# kbd.net
KiCad netlist of a schematic drawn in Altium Designer
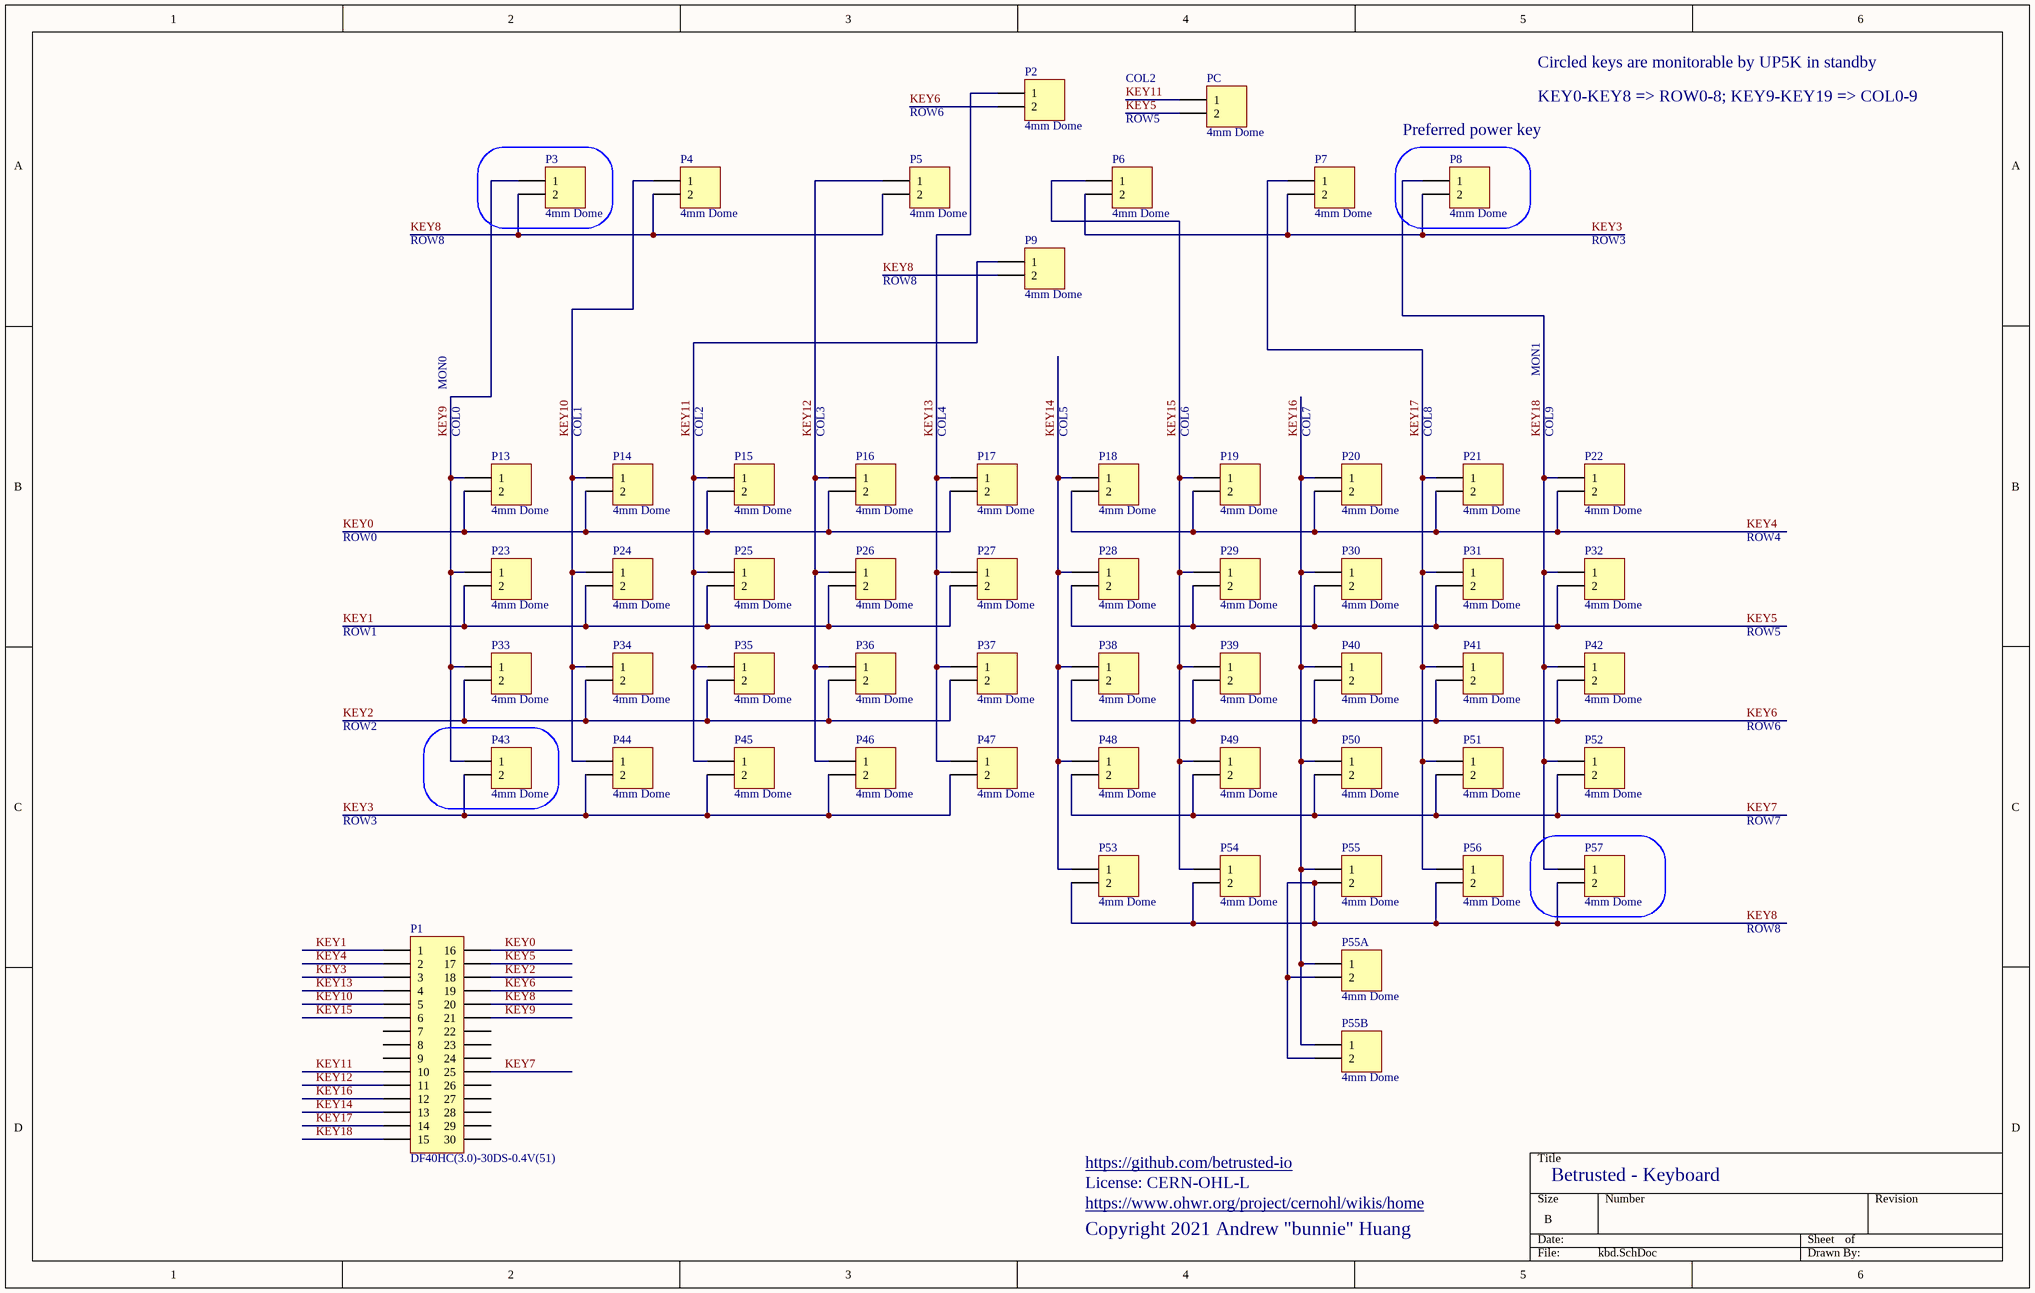
[diagram p0: kbd.SchDoc]

(export (version "E")
  (design (tool "Eeschema 10.0.6"))
  (components
    (comp (ref "P1")
      (value "DF40HC(3.0)-30DS-0.4V(51)")
      (footprint "HRS_DF40HC(3.0)-30DS-0.4V(51)")
      (description "Header, 15-Pin, Dual row")
      (fields (field (name "PUBLISHER") "Altium Limited"))
      (libsource (lib "Miscellaneous Connectors") (part "Header 15X2A"))
    )
    (comp (ref "P2")
      (value "4mm Dome")
      (footprint "4MM_DOME_SW")
      (description "Header, 2-Pin")
      (fields (field (name "PUBLISHER") "Altium Limited"))
      (libsource (lib "Miscellaneous Connectors") (part "Header 2"))
    )
    (comp (ref "P3")
      (value "4mm Dome")
      (footprint "4MM_DOME_SW")
      (description "Header, 2-Pin")
      (fields (field (name "PUBLISHER") "Altium Limited"))
      (libsource (lib "Miscellaneous Connectors") (part "Header 2"))
    )
    (comp (ref "P4")
      (value "4mm Dome")
      (footprint "4MM_DOME_SW")
      (description "Header, 2-Pin")
      (fields (field (name "PUBLISHER") "Altium Limited"))
      (libsource (lib "Miscellaneous Connectors") (part "Header 2"))
    )
    (comp (ref "P5")
      (value "4mm Dome")
      (footprint "4MM_DOME_SW")
      (description "Header, 2-Pin")
      (fields (field (name "PUBLISHER") "Altium Limited"))
      (libsource (lib "Miscellaneous Connectors") (part "Header 2"))
    )
    (comp (ref "P6")
      (value "4mm Dome")
      (footprint "4MM_DOME_SW")
      (description "Header, 2-Pin")
      (fields (field (name "PUBLISHER") "Altium Limited"))
      (libsource (lib "Miscellaneous Connectors") (part "Header 2"))
    )
    (comp (ref "P7")
      (value "4mm Dome")
      (footprint "4MM_DOME_SW")
      (description "Header, 2-Pin")
      (fields (field (name "PUBLISHER") "Altium Limited"))
      (libsource (lib "Miscellaneous Connectors") (part "Header 2"))
    )
    (comp (ref "P8")
      (value "4mm Dome")
      (footprint "4MM_DOME_SW")
      (description "Header, 2-Pin")
      (fields (field (name "PUBLISHER") "Altium Limited"))
      (libsource (lib "Miscellaneous Connectors") (part "Header 2"))
    )
    (comp (ref "P9")
      (value "4mm Dome")
      (footprint "4MM_DOME_SW")
      (description "Header, 2-Pin")
      (fields (field (name "PUBLISHER") "Altium Limited"))
      (libsource (lib "Miscellaneous Connectors") (part "Header 2"))
    )
    (comp (ref "P13")
      (value "4mm Dome")
      (footprint "4MM_DOME_SW")
      (description "Header, 2-Pin")
      (fields (field (name "PUBLISHER") "Altium Limited"))
      (libsource (lib "Miscellaneous Connectors") (part "Header 2"))
    )
    (comp (ref "P14")
      (value "4mm Dome")
      (footprint "4MM_DOME_SW")
      (description "Header, 2-Pin")
      (fields (field (name "PUBLISHER") "Altium Limited"))
      (libsource (lib "Miscellaneous Connectors") (part "Header 2"))
    )
    (comp (ref "P15")
      (value "4mm Dome")
      (footprint "4MM_DOME_SW")
      (description "Header, 2-Pin")
      (fields (field (name "PUBLISHER") "Altium Limited"))
      (libsource (lib "Miscellaneous Connectors") (part "Header 2"))
    )
    (comp (ref "P16")
      (value "4mm Dome")
      (footprint "4MM_DOME_SW")
      (description "Header, 2-Pin")
      (fields (field (name "PUBLISHER") "Altium Limited"))
      (libsource (lib "Miscellaneous Connectors") (part "Header 2"))
    )
    (comp (ref "P17")
      (value "4mm Dome")
      (footprint "4MM_DOME_SW")
      (description "Header, 2-Pin")
      (fields (field (name "PUBLISHER") "Altium Limited"))
      (libsource (lib "Miscellaneous Connectors") (part "Header 2"))
    )
    (comp (ref "P18")
      (value "4mm Dome")
      (footprint "4MM_DOME_SW")
      (description "Header, 2-Pin")
      (fields (field (name "PUBLISHER") "Altium Limited"))
      (libsource (lib "Miscellaneous Connectors") (part "Header 2"))
    )
    (comp (ref "P19")
      (value "4mm Dome")
      (footprint "4MM_DOME_SW")
      (description "Header, 2-Pin")
      (fields (field (name "PUBLISHER") "Altium Limited"))
      (libsource (lib "Miscellaneous Connectors") (part "Header 2"))
    )
    (comp (ref "P20")
      (value "4mm Dome")
      (footprint "4MM_DOME_SW")
      (description "Header, 2-Pin")
      (fields (field (name "PUBLISHER") "Altium Limited"))
      (libsource (lib "Miscellaneous Connectors") (part "Header 2"))
    )
    (comp (ref "P21")
      (value "4mm Dome")
      (footprint "4MM_DOME_SW")
      (description "Header, 2-Pin")
      (fields (field (name "PUBLISHER") "Altium Limited"))
      (libsource (lib "Miscellaneous Connectors") (part "Header 2"))
    )
    (comp (ref "P22")
      (value "4mm Dome")
      (footprint "4MM_DOME_SW")
      (description "Header, 2-Pin")
      (fields (field (name "PUBLISHER") "Altium Limited"))
      (libsource (lib "Miscellaneous Connectors") (part "Header 2"))
    )
    (comp (ref "P23")
      (value "4mm Dome")
      (footprint "4MM_DOME_SW")
      (description "Header, 2-Pin")
      (fields (field (name "PUBLISHER") "Altium Limited"))
      (libsource (lib "Miscellaneous Connectors") (part "Header 2"))
    )
    (comp (ref "P24")
      (value "4mm Dome")
      (footprint "4MM_DOME_SW")
      (description "Header, 2-Pin")
      (fields (field (name "PUBLISHER") "Altium Limited"))
      (libsource (lib "Miscellaneous Connectors") (part "Header 2"))
    )
    (comp (ref "P25")
      (value "4mm Dome")
      (footprint "4MM_DOME_SW")
      (description "Header, 2-Pin")
      (fields (field (name "PUBLISHER") "Altium Limited"))
      (libsource (lib "Miscellaneous Connectors") (part "Header 2"))
    )
    (comp (ref "P26")
      (value "4mm Dome")
      (footprint "4MM_DOME_SW")
      (description "Header, 2-Pin")
      (fields (field (name "PUBLISHER") "Altium Limited"))
      (libsource (lib "Miscellaneous Connectors") (part "Header 2"))
    )
    (comp (ref "P27")
      (value "4mm Dome")
      (footprint "4MM_DOME_SW")
      (description "Header, 2-Pin")
      (fields (field (name "PUBLISHER") "Altium Limited"))
      (libsource (lib "Miscellaneous Connectors") (part "Header 2"))
    )
    (comp (ref "P28")
      (value "4mm Dome")
      (footprint "4MM_DOME_SW")
      (description "Header, 2-Pin")
      (fields (field (name "PUBLISHER") "Altium Limited"))
      (libsource (lib "Miscellaneous Connectors") (part "Header 2"))
    )
    (comp (ref "P29")
      (value "4mm Dome")
      (footprint "4MM_DOME_SW")
      (description "Header, 2-Pin")
      (fields (field (name "PUBLISHER") "Altium Limited"))
      (libsource (lib "Miscellaneous Connectors") (part "Header 2"))
    )
    (comp (ref "P30")
      (value "4mm Dome")
      (footprint "4MM_DOME_SW")
      (description "Header, 2-Pin")
      (fields (field (name "PUBLISHER") "Altium Limited"))
      (libsource (lib "Miscellaneous Connectors") (part "Header 2"))
    )
    (comp (ref "P31")
      (value "4mm Dome")
      (footprint "4MM_DOME_SW")
      (description "Header, 2-Pin")
      (fields (field (name "PUBLISHER") "Altium Limited"))
      (libsource (lib "Miscellaneous Connectors") (part "Header 2"))
    )
    (comp (ref "P32")
      (value "4mm Dome")
      (footprint "4MM_DOME_SW")
      (description "Header, 2-Pin")
      (fields (field (name "PUBLISHER") "Altium Limited"))
      (libsource (lib "Miscellaneous Connectors") (part "Header 2"))
    )
    (comp (ref "P33")
      (value "4mm Dome")
      (footprint "4MM_DOME_SW")
      (description "Header, 2-Pin")
      (fields (field (name "PUBLISHER") "Altium Limited"))
      (libsource (lib "Miscellaneous Connectors") (part "Header 2"))
    )
    (comp (ref "P34")
      (value "4mm Dome")
      (footprint "4MM_DOME_SW")
      (description "Header, 2-Pin")
      (fields (field (name "PUBLISHER") "Altium Limited"))
      (libsource (lib "Miscellaneous Connectors") (part "Header 2"))
    )
    (comp (ref "P35")
      (value "4mm Dome")
      (footprint "4MM_DOME_SW")
      (description "Header, 2-Pin")
      (fields (field (name "PUBLISHER") "Altium Limited"))
      (libsource (lib "Miscellaneous Connectors") (part "Header 2"))
    )
    (comp (ref "P36")
      (value "4mm Dome")
      (footprint "4MM_DOME_SW")
      (description "Header, 2-Pin")
      (fields (field (name "PUBLISHER") "Altium Limited"))
      (libsource (lib "Miscellaneous Connectors") (part "Header 2"))
    )
    (comp (ref "P37")
      (value "4mm Dome")
      (footprint "4MM_DOME_SW")
      (description "Header, 2-Pin")
      (fields (field (name "PUBLISHER") "Altium Limited"))
      (libsource (lib "Miscellaneous Connectors") (part "Header 2"))
    )
    (comp (ref "P38")
      (value "4mm Dome")
      (footprint "4MM_DOME_SW")
      (description "Header, 2-Pin")
      (fields (field (name "PUBLISHER") "Altium Limited"))
      (libsource (lib "Miscellaneous Connectors") (part "Header 2"))
    )
    (comp (ref "P39")
      (value "4mm Dome")
      (footprint "4MM_DOME_SW")
      (description "Header, 2-Pin")
      (fields (field (name "PUBLISHER") "Altium Limited"))
      (libsource (lib "Miscellaneous Connectors") (part "Header 2"))
    )
    (comp (ref "P40")
      (value "4mm Dome")
      (footprint "4MM_DOME_SW")
      (description "Header, 2-Pin")
      (fields (field (name "PUBLISHER") "Altium Limited"))
      (libsource (lib "Miscellaneous Connectors") (part "Header 2"))
    )
    (comp (ref "P41")
      (value "4mm Dome")
      (footprint "4MM_DOME_SW")
      (description "Header, 2-Pin")
      (fields (field (name "PUBLISHER") "Altium Limited"))
      (libsource (lib "Miscellaneous Connectors") (part "Header 2"))
    )
    (comp (ref "P42")
      (value "4mm Dome")
      (footprint "4MM_DOME_SW")
      (description "Header, 2-Pin")
      (fields (field (name "PUBLISHER") "Altium Limited"))
      (libsource (lib "Miscellaneous Connectors") (part "Header 2"))
    )
    (comp (ref "P43")
      (value "4mm Dome")
      (footprint "4MM_DOME_SW")
      (description "Header, 2-Pin")
      (fields (field (name "PUBLISHER") "Altium Limited"))
      (libsource (lib "Miscellaneous Connectors") (part "Header 2"))
    )
    (comp (ref "P44")
      (value "4mm Dome")
      (footprint "4MM_DOME_SW")
      (description "Header, 2-Pin")
      (fields (field (name "PUBLISHER") "Altium Limited"))
      (libsource (lib "Miscellaneous Connectors") (part "Header 2"))
    )
    (comp (ref "P45")
      (value "4mm Dome")
      (footprint "4MM_DOME_SW")
      (description "Header, 2-Pin")
      (fields (field (name "PUBLISHER") "Altium Limited"))
      (libsource (lib "Miscellaneous Connectors") (part "Header 2"))
    )
    (comp (ref "P46")
      (value "4mm Dome")
      (footprint "4MM_DOME_SW")
      (description "Header, 2-Pin")
      (fields (field (name "PUBLISHER") "Altium Limited"))
      (libsource (lib "Miscellaneous Connectors") (part "Header 2"))
    )
    (comp (ref "P47")
      (value "4mm Dome")
      (footprint "4MM_DOME_SW")
      (description "Header, 2-Pin")
      (fields (field (name "PUBLISHER") "Altium Limited"))
      (libsource (lib "Miscellaneous Connectors") (part "Header 2"))
    )
    (comp (ref "P48")
      (value "4mm Dome")
      (footprint "4MM_DOME_SW")
      (description "Header, 2-Pin")
      (fields (field (name "PUBLISHER") "Altium Limited"))
      (libsource (lib "Miscellaneous Connectors") (part "Header 2"))
    )
    (comp (ref "P49")
      (value "4mm Dome")
      (footprint "4MM_DOME_SW")
      (description "Header, 2-Pin")
      (fields (field (name "PUBLISHER") "Altium Limited"))
      (libsource (lib "Miscellaneous Connectors") (part "Header 2"))
    )
    (comp (ref "P50")
      (value "4mm Dome")
      (footprint "4MM_DOME_SW")
      (description "Header, 2-Pin")
      (fields (field (name "PUBLISHER") "Altium Limited"))
      (libsource (lib "Miscellaneous Connectors") (part "Header 2"))
    )
    (comp (ref "P51")
      (value "4mm Dome")
      (footprint "4MM_DOME_SW")
      (description "Header, 2-Pin")
      (fields (field (name "PUBLISHER") "Altium Limited"))
      (libsource (lib "Miscellaneous Connectors") (part "Header 2"))
    )
    (comp (ref "P52")
      (value "4mm Dome")
      (footprint "4MM_DOME_SW")
      (description "Header, 2-Pin")
      (fields (field (name "PUBLISHER") "Altium Limited"))
      (libsource (lib "Miscellaneous Connectors") (part "Header 2"))
    )
    (comp (ref "P53")
      (value "4mm Dome")
      (footprint "4MM_DOME_SW")
      (description "Header, 2-Pin")
      (fields (field (name "PUBLISHER") "Altium Limited"))
      (libsource (lib "Miscellaneous Connectors") (part "Header 2"))
    )
    (comp (ref "P54")
      (value "4mm Dome")
      (footprint "4MM_DOME_SW")
      (description "Header, 2-Pin")
      (fields (field (name "PUBLISHER") "Altium Limited"))
      (libsource (lib "Miscellaneous Connectors") (part "Header 2"))
    )
    (comp (ref "P55")
      (value "4mm Dome")
      (footprint "4MM_DOME_SW")
      (description "Header, 2-Pin")
      (fields (field (name "PUBLISHER") "Altium Limited"))
      (libsource (lib "Miscellaneous Connectors") (part "Header 2"))
    )
    (comp (ref "P55A")
      (value "4mm Dome")
      (footprint "4MM_DOME_SW")
      (description "Header, 2-Pin")
      (fields (field (name "PUBLISHER") "Altium Limited"))
      (libsource (lib "Miscellaneous Connectors") (part "Header 2"))
    )
    (comp (ref "P55B")
      (value "4mm Dome")
      (footprint "4MM_DOME_SW")
      (description "Header, 2-Pin")
      (fields (field (name "PUBLISHER") "Altium Limited"))
      (libsource (lib "Miscellaneous Connectors") (part "Header 2"))
    )
    (comp (ref "P56")
      (value "4mm Dome")
      (footprint "4MM_DOME_SW")
      (description "Header, 2-Pin")
      (fields (field (name "PUBLISHER") "Altium Limited"))
      (libsource (lib "Miscellaneous Connectors") (part "Header 2"))
    )
    (comp (ref "P57")
      (value "4mm Dome")
      (footprint "4MM_DOME_SW")
      (description "Header, 2-Pin")
      (fields (field (name "PUBLISHER") "Altium Limited"))
      (libsource (lib "Miscellaneous Connectors") (part "Header 2"))
    )
    (comp (ref "PC")
      (value "4mm Dome")
      (footprint "4MM_DOME_SW")
      (description "Header, 2-Pin")
      (fields (field (name "PUBLISHER") "Altium Limited"))
      (libsource (lib "Miscellaneous Connectors") (part "Header 2"))
    )
  )
  (nets
    (net (code "1") (name "/KEY0") (class "Default")
      (node (ref "P1") (pin "16") (pinfunction "16_16") (pintype "passive"))
      (node (ref "P13") (pin "2") (pinfunction "2_2") (pintype "passive"))
      (node (ref "P14") (pin "2") (pinfunction "2_2") (pintype "passive"))
      (node (ref "P15") (pin "2") (pinfunction "2_2") (pintype "passive"))
      (node (ref "P16") (pin "2") (pinfunction "2_2") (pintype "passive"))
      (node (ref "P17") (pin "2") (pinfunction "2_2") (pintype "passive"))
    )
    (net (code "2") (name "/KEY1") (class "Default")
      (node (ref "P1") (pin "1") (pinfunction "1_1") (pintype "passive"))
      (node (ref "P23") (pin "2") (pinfunction "2_2") (pintype "passive"))
      (node (ref "P24") (pin "2") (pinfunction "2_2") (pintype "passive"))
      (node (ref "P25") (pin "2") (pinfunction "2_2") (pintype "passive"))
      (node (ref "P26") (pin "2") (pinfunction "2_2") (pintype "passive"))
      (node (ref "P27") (pin "2") (pinfunction "2_2") (pintype "passive"))
    )
    (net (code "3") (name "/KEY2") (class "Default")
      (node (ref "P1") (pin "18") (pinfunction "18_18") (pintype "passive"))
      (node (ref "P33") (pin "2") (pinfunction "2_2") (pintype "passive"))
      (node (ref "P34") (pin "2") (pinfunction "2_2") (pintype "passive"))
      (node (ref "P35") (pin "2") (pinfunction "2_2") (pintype "passive"))
      (node (ref "P36") (pin "2") (pinfunction "2_2") (pintype "passive"))
      (node (ref "P37") (pin "2") (pinfunction "2_2") (pintype "passive"))
    )
    (net (code "4") (name "/KEY3") (class "Default")
      (node (ref "P1") (pin "3") (pinfunction "3_3") (pintype "passive"))
      (node (ref "P43") (pin "2") (pinfunction "2_2") (pintype "passive"))
      (node (ref "P44") (pin "2") (pinfunction "2_2") (pintype "passive"))
      (node (ref "P45") (pin "2") (pinfunction "2_2") (pintype "passive"))
      (node (ref "P46") (pin "2") (pinfunction "2_2") (pintype "passive"))
      (node (ref "P47") (pin "2") (pinfunction "2_2") (pintype "passive"))
      (node (ref "P6") (pin "2") (pinfunction "2_2") (pintype "passive"))
      (node (ref "P7") (pin "2") (pinfunction "2_2") (pintype "passive"))
      (node (ref "P8") (pin "2") (pinfunction "2_2") (pintype "passive"))
    )
    (net (code "5") (name "/KEY4") (class "Default")
      (node (ref "P1") (pin "2") (pinfunction "2_2") (pintype "passive"))
      (node (ref "P18") (pin "2") (pinfunction "2_2") (pintype "passive"))
      (node (ref "P19") (pin "2") (pinfunction "2_2") (pintype "passive"))
      (node (ref "P20") (pin "2") (pinfunction "2_2") (pintype "passive"))
      (node (ref "P21") (pin "2") (pinfunction "2_2") (pintype "passive"))
      (node (ref "P22") (pin "2") (pinfunction "2_2") (pintype "passive"))
    )
    (net (code "6") (name "/KEY5") (class "Default")
      (node (ref "P1") (pin "17") (pinfunction "17_17") (pintype "passive"))
      (node (ref "P28") (pin "2") (pinfunction "2_2") (pintype "passive"))
      (node (ref "P29") (pin "2") (pinfunction "2_2") (pintype "passive"))
      (node (ref "P30") (pin "2") (pinfunction "2_2") (pintype "passive"))
      (node (ref "P31") (pin "2") (pinfunction "2_2") (pintype "passive"))
      (node (ref "P32") (pin "2") (pinfunction "2_2") (pintype "passive"))
      (node (ref "PC") (pin "2") (pinfunction "2_2") (pintype "passive"))
    )
    (net (code "7") (name "/KEY6") (class "Default")
      (node (ref "P1") (pin "19") (pinfunction "19_19") (pintype "passive"))
      (node (ref "P2") (pin "2") (pinfunction "2_2") (pintype "passive"))
      (node (ref "P38") (pin "2") (pinfunction "2_2") (pintype "passive"))
      (node (ref "P39") (pin "2") (pinfunction "2_2") (pintype "passive"))
      (node (ref "P40") (pin "2") (pinfunction "2_2") (pintype "passive"))
      (node (ref "P41") (pin "2") (pinfunction "2_2") (pintype "passive"))
      (node (ref "P42") (pin "2") (pinfunction "2_2") (pintype "passive"))
    )
    (net (code "8") (name "/KEY7") (class "Default")
      (node (ref "P1") (pin "25") (pinfunction "25_25") (pintype "passive"))
      (node (ref "P48") (pin "2") (pinfunction "2_2") (pintype "passive"))
      (node (ref "P49") (pin "2") (pinfunction "2_2") (pintype "passive"))
      (node (ref "P50") (pin "2") (pinfunction "2_2") (pintype "passive"))
      (node (ref "P51") (pin "2") (pinfunction "2_2") (pintype "passive"))
      (node (ref "P52") (pin "2") (pinfunction "2_2") (pintype "passive"))
    )
    (net (code "9") (name "/KEY8") (class "Default")
      (node (ref "P1") (pin "20") (pinfunction "20_20") (pintype "passive"))
      (node (ref "P3") (pin "2") (pinfunction "2_2") (pintype "passive"))
      (node (ref "P4") (pin "2") (pinfunction "2_2") (pintype "passive"))
      (node (ref "P5") (pin "2") (pinfunction "2_2") (pintype "passive"))
      (node (ref "P53") (pin "2") (pinfunction "2_2") (pintype "passive"))
      (node (ref "P54") (pin "2") (pinfunction "2_2") (pintype "passive"))
      (node (ref "P55") (pin "2") (pinfunction "2_2") (pintype "passive"))
      (node (ref "P55A") (pin "2") (pinfunction "2_2") (pintype "passive"))
      (node (ref "P55B") (pin "2") (pinfunction "2_2") (pintype "passive"))
      (node (ref "P56") (pin "2") (pinfunction "2_2") (pintype "passive"))
      (node (ref "P57") (pin "2") (pinfunction "2_2") (pintype "passive"))
      (node (ref "P9") (pin "2") (pinfunction "2_2") (pintype "passive"))
    )
    (net (code "10") (name "/KEY9") (class "Default")
      (node (ref "P1") (pin "21") (pinfunction "21_21") (pintype "passive"))
      (node (ref "P13") (pin "1") (pinfunction "1_1") (pintype "passive"))
      (node (ref "P23") (pin "1") (pinfunction "1_1") (pintype "passive"))
      (node (ref "P3") (pin "1") (pinfunction "1_1") (pintype "passive"))
      (node (ref "P33") (pin "1") (pinfunction "1_1") (pintype "passive"))
      (node (ref "P43") (pin "1") (pinfunction "1_1") (pintype "passive"))
    )
    (net (code "11") (name "/KEY10") (class "Default")
      (node (ref "P1") (pin "5") (pinfunction "5_5") (pintype "passive"))
      (node (ref "P14") (pin "1") (pinfunction "1_1") (pintype "passive"))
      (node (ref "P24") (pin "1") (pinfunction "1_1") (pintype "passive"))
      (node (ref "P34") (pin "1") (pinfunction "1_1") (pintype "passive"))
      (node (ref "P4") (pin "1") (pinfunction "1_1") (pintype "passive"))
      (node (ref "P44") (pin "1") (pinfunction "1_1") (pintype "passive"))
    )
    (net (code "12") (name "/KEY11") (class "Default")
      (node (ref "P1") (pin "10") (pinfunction "10_10") (pintype "passive"))
      (node (ref "P15") (pin "1") (pinfunction "1_1") (pintype "passive"))
      (node (ref "P25") (pin "1") (pinfunction "1_1") (pintype "passive"))
      (node (ref "P35") (pin "1") (pinfunction "1_1") (pintype "passive"))
      (node (ref "P45") (pin "1") (pinfunction "1_1") (pintype "passive"))
      (node (ref "P9") (pin "1") (pinfunction "1_1") (pintype "passive"))
      (node (ref "PC") (pin "1") (pinfunction "1_1") (pintype "passive"))
    )
    (net (code "13") (name "/KEY12") (class "Default")
      (node (ref "P1") (pin "11") (pinfunction "11_11") (pintype "passive"))
      (node (ref "P16") (pin "1") (pinfunction "1_1") (pintype "passive"))
      (node (ref "P26") (pin "1") (pinfunction "1_1") (pintype "passive"))
      (node (ref "P36") (pin "1") (pinfunction "1_1") (pintype "passive"))
      (node (ref "P46") (pin "1") (pinfunction "1_1") (pintype "passive"))
      (node (ref "P5") (pin "1") (pinfunction "1_1") (pintype "passive"))
    )
    (net (code "14") (name "/KEY13") (class "Default")
      (node (ref "P1") (pin "4") (pinfunction "4_4") (pintype "passive"))
      (node (ref "P17") (pin "1") (pinfunction "1_1") (pintype "passive"))
      (node (ref "P2") (pin "1") (pinfunction "1_1") (pintype "passive"))
      (node (ref "P27") (pin "1") (pinfunction "1_1") (pintype "passive"))
      (node (ref "P37") (pin "1") (pinfunction "1_1") (pintype "passive"))
      (node (ref "P47") (pin "1") (pinfunction "1_1") (pintype "passive"))
    )
    (net (code "15") (name "/KEY14") (class "Default")
      (node (ref "P1") (pin "13") (pinfunction "13_13") (pintype "passive"))
      (node (ref "P18") (pin "1") (pinfunction "1_1") (pintype "passive"))
      (node (ref "P28") (pin "1") (pinfunction "1_1") (pintype "passive"))
      (node (ref "P38") (pin "1") (pinfunction "1_1") (pintype "passive"))
      (node (ref "P48") (pin "1") (pinfunction "1_1") (pintype "passive"))
      (node (ref "P53") (pin "1") (pinfunction "1_1") (pintype "passive"))
    )
    (net (code "16") (name "/KEY15") (class "Default")
      (node (ref "P1") (pin "6") (pinfunction "6_6") (pintype "passive"))
      (node (ref "P19") (pin "1") (pinfunction "1_1") (pintype "passive"))
      (node (ref "P29") (pin "1") (pinfunction "1_1") (pintype "passive"))
      (node (ref "P39") (pin "1") (pinfunction "1_1") (pintype "passive"))
      (node (ref "P49") (pin "1") (pinfunction "1_1") (pintype "passive"))
      (node (ref "P54") (pin "1") (pinfunction "1_1") (pintype "passive"))
      (node (ref "P6") (pin "1") (pinfunction "1_1") (pintype "passive"))
    )
    (net (code "17") (name "/KEY16") (class "Default")
      (node (ref "P1") (pin "12") (pinfunction "12_12") (pintype "passive"))
      (node (ref "P20") (pin "1") (pinfunction "1_1") (pintype "passive"))
      (node (ref "P30") (pin "1") (pinfunction "1_1") (pintype "passive"))
      (node (ref "P40") (pin "1") (pinfunction "1_1") (pintype "passive"))
      (node (ref "P50") (pin "1") (pinfunction "1_1") (pintype "passive"))
      (node (ref "P55") (pin "1") (pinfunction "1_1") (pintype "passive"))
      (node (ref "P55A") (pin "1") (pinfunction "1_1") (pintype "passive"))
      (node (ref "P55B") (pin "1") (pinfunction "1_1") (pintype "passive"))
    )
    (net (code "18") (name "/KEY17") (class "Default")
      (node (ref "P1") (pin "14") (pinfunction "14_14") (pintype "passive"))
      (node (ref "P21") (pin "1") (pinfunction "1_1") (pintype "passive"))
      (node (ref "P31") (pin "1") (pinfunction "1_1") (pintype "passive"))
      (node (ref "P41") (pin "1") (pinfunction "1_1") (pintype "passive"))
      (node (ref "P51") (pin "1") (pinfunction "1_1") (pintype "passive"))
      (node (ref "P56") (pin "1") (pinfunction "1_1") (pintype "passive"))
      (node (ref "P7") (pin "1") (pinfunction "1_1") (pintype "passive"))
    )
    (net (code "19") (name "/KEY18") (class "Default")
      (node (ref "P1") (pin "15") (pinfunction "15_15") (pintype "passive"))
      (node (ref "P22") (pin "1") (pinfunction "1_1") (pintype "passive"))
      (node (ref "P32") (pin "1") (pinfunction "1_1") (pintype "passive"))
      (node (ref "P42") (pin "1") (pinfunction "1_1") (pintype "passive"))
      (node (ref "P52") (pin "1") (pinfunction "1_1") (pintype "passive"))
      (node (ref "P57") (pin "1") (pinfunction "1_1") (pintype "passive"))
      (node (ref "P8") (pin "1") (pinfunction "1_1") (pintype "passive"))
    )
    (net (code "20") (name "unconnected-(P1-Pad7)") (class "Default")
      (node (ref "P1") (pin "7") (pinfunction "7_7") (pintype "passive"))
    )
    (net (code "21") (name "unconnected-(P1-Pad8)") (class "Default")
      (node (ref "P1") (pin "8") (pinfunction "8_8") (pintype "passive"))
    )
    (net (code "22") (name "unconnected-(P1-Pad9)") (class "Default")
      (node (ref "P1") (pin "9") (pinfunction "9_9") (pintype "passive"))
    )
    (net (code "23") (name "unconnected-(P1-Pad22)") (class "Default")
      (node (ref "P1") (pin "22") (pinfunction "22_22") (pintype "passive"))
    )
    (net (code "24") (name "unconnected-(P1-Pad23)") (class "Default")
      (node (ref "P1") (pin "23") (pinfunction "23_23") (pintype "passive"))
    )
    (net (code "25") (name "unconnected-(P1-Pad24)") (class "Default")
      (node (ref "P1") (pin "24") (pinfunction "24_24") (pintype "passive"))
    )
    (net (code "26") (name "unconnected-(P1-Pad26)") (class "Default")
      (node (ref "P1") (pin "26") (pinfunction "26_26") (pintype "passive"))
    )
    (net (code "27") (name "unconnected-(P1-Pad27)") (class "Default")
      (node (ref "P1") (pin "27") (pinfunction "27_27") (pintype "passive"))
    )
    (net (code "28") (name "unconnected-(P1-Pad28)") (class "Default")
      (node (ref "P1") (pin "28") (pinfunction "28_28") (pintype "passive"))
    )
    (net (code "29") (name "unconnected-(P1-Pad29)") (class "Default")
      (node (ref "P1") (pin "29") (pinfunction "29_29") (pintype "passive"))
    )
    (net (code "30") (name "unconnected-(P1-Pad30)") (class "Default")
      (node (ref "P1") (pin "30") (pinfunction "30_30") (pintype "passive"))
    )
  )
)
